# STeaMi-FP6-Microcontroleur.net
KiCad netlist of a schematic drawn in Altium Designer
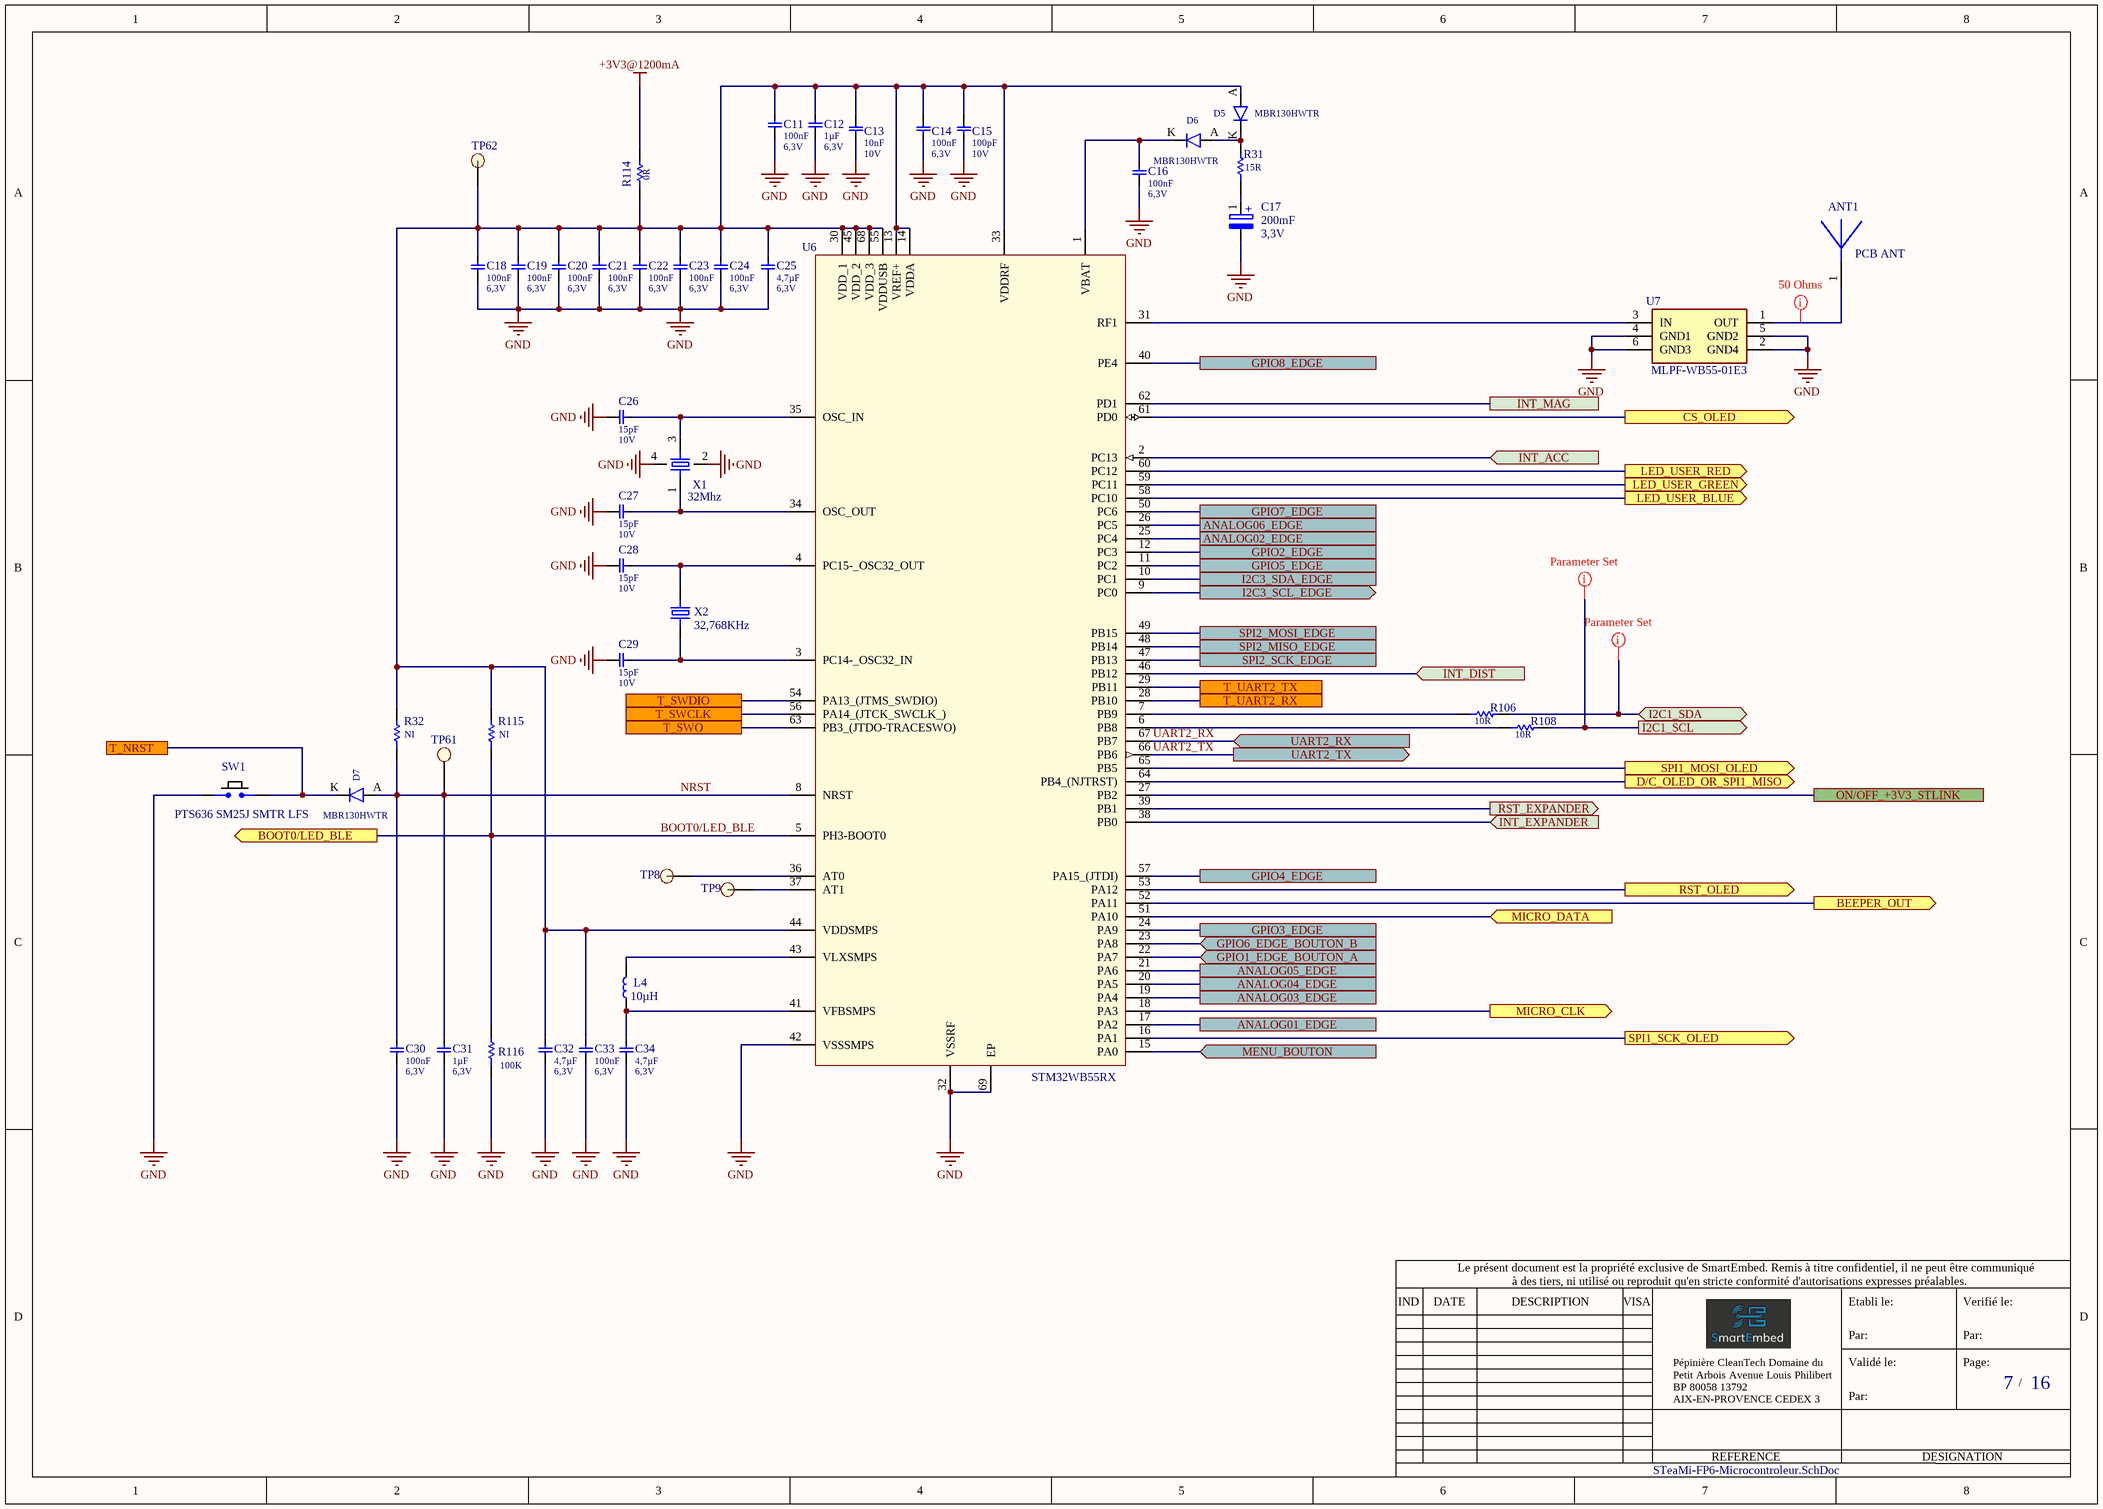
[diagram p0: STeaMi-FP6-Microcontroleur.SchDoc]

(export (version "E")
  (design (tool "Eeschema 10.0.6"))
  (components
    (comp (ref "ANT1")
      (value "PCB ANT")
      (footprint "PCB_ANT")
      (description "PCB ANTENAL")
      (fields (field (name "PART NUMBER") "PCB_ANT") (field (name "CREATED BY") "EAG"))
      (libsource (lib "ComponentDB") (part "NN01-102"))
    )
    (comp (ref "C11")
      (value "~")
      (footprint "0402-CAP")
      (description "CAP CER 100nF 6,3V X5R 0402")
      (fields
        (field (name "MANUFACTURER") "Kyocera AVX")
        (field (name "MANUFACTURER PART NUMBER") "0402YD104KAT2A")
        (field (name "CAPACITANCE") "100nF")
        (field (name "VOLTAGE") "6,3V")
        (field (name "CREATED BY") "EAG")
        (field (name "CHECKED BY") "*")
      )
      (libsource (lib "ComponentDB") (part "CAP_SYMBOL"))
    )
    (comp (ref "C12")
      (value "~")
      (footprint "0402-CAP")
      (description "CAP CER 1µF 6,3V X5R 0402")
      (fields
        (field (name "MANUFACTURER") "Taiyo Yuden")
        (field (name "MANUFACTURER PART NUMBER") "JMK105BJ105KV-F")
        (field (name "CAPACITANCE") "1µF")
        (field (name "VOLTAGE") "6,3V")
        (field (name "CREATED BY") "EAG")
        (field (name "CHECKED BY") "*")
      )
      (libsource (lib "ComponentDB") (part "CAP_SYMBOL"))
    )
    (comp (ref "C13")
      (value "~")
      (footprint "0402-CAP")
      (description "CAP CER 10nF 10V X7R 0402")
      (fields
        (field (name "MANUFACTURER") "AVX")
        (field (name "MANUFACTURER PART NUMBER") "0402ZC103KAT2A")
        (field (name "CAPACITANCE") "10nF")
        (field (name "VOLTAGE") "10V")
        (field (name "CREATED BY") "EAG")
        (field (name "CHECKED BY") "*")
      )
      (libsource (lib "ComponentDB") (part "CAP_SYMBOL"))
    )
    (comp (ref "C14")
      (value "~")
      (footprint "0402-CAP")
      (description "CAP CER 100nF 6,3V X5R 0402")
      (fields
        (field (name "MANUFACTURER") "Kyocera AVX")
        (field (name "MANUFACTURER PART NUMBER") "0402YD104KAT2A")
        (field (name "CAPACITANCE") "100nF")
        (field (name "VOLTAGE") "6,3V")
        (field (name "CREATED BY") "EAG")
        (field (name "CHECKED BY") "*")
      )
      (libsource (lib "ComponentDB") (part "CAP_SYMBOL"))
    )
    (comp (ref "C15")
      (value "~")
      (footprint "0402-CAP")
      (description "CAP CER 100pF 10V X7R 0402")
      (fields
        (field (name "MANUFACTURER") "WURTH Electronics")
        (field (name "MANUFACTURER PART NUMBER") "885012205001")
        (field (name "CAPACITANCE") "100pF")
        (field (name "VOLTAGE") "10V")
        (field (name "CREATED BY") "EAG")
        (field (name "CHECKED BY") "*")
      )
      (libsource (lib "ComponentDB") (part "CAP_SYMBOL"))
    )
    (comp (ref "C16")
      (value "~")
      (footprint "0402-CAP")
      (description "CAP CER 100nF 6,3V X5R 0402")
      (fields
        (field (name "MANUFACTURER") "Kyocera AVX")
        (field (name "MANUFACTURER PART NUMBER") "0402YD104KAT2A")
        (field (name "CAPACITANCE") "100nF")
        (field (name "VOLTAGE") "6,3V")
        (field (name "CREATED BY") "EAG")
        (field (name "CHECKED BY") "*")
      )
      (libsource (lib "ComponentDB") (part "CAP_SYMBOL"))
    )
    (comp (ref "C17")
      (value "~")
      (footprint "DSK3R3H204T614")
      (description "CAP CER 200mF 3,3V Supercap 6,8X11,7x1,8")
      (fields
        (field (name "MANUFACTURER") "Elna America")
        (field (name "MANUFACTURER PART NUMBER") "DSK-3R3H204T614-H2L")
        (field (name "CAPACITANCE") "200mF")
        (field (name "VOLTAGE") "3,3V")
        (field (name "CREATED BY") "EAG")
      )
      (libsource (lib "ComponentDB") (part "CAP_POL_SYMBOL"))
    )
    (comp (ref "C18")
      (value "~")
      (footprint "0402-CAP")
      (description "CAP CER 100nF 6,3V X5R 0402")
      (fields
        (field (name "MANUFACTURER") "Kyocera AVX")
        (field (name "MANUFACTURER PART NUMBER") "0402YD104KAT2A")
        (field (name "CAPACITANCE") "100nF")
        (field (name "VOLTAGE") "6,3V")
        (field (name "CREATED BY") "EAG")
        (field (name "CHECKED BY") "*")
      )
      (libsource (lib "ComponentDB") (part "CAP_SYMBOL"))
    )
    (comp (ref "C19")
      (value "~")
      (footprint "0402-CAP")
      (description "CAP CER 100nF 6,3V X5R 0402")
      (fields
        (field (name "MANUFACTURER") "Kyocera AVX")
        (field (name "MANUFACTURER PART NUMBER") "0402YD104KAT2A")
        (field (name "CAPACITANCE") "100nF")
        (field (name "VOLTAGE") "6,3V")
        (field (name "CREATED BY") "EAG")
        (field (name "CHECKED BY") "*")
      )
      (libsource (lib "ComponentDB") (part "CAP_SYMBOL"))
    )
    (comp (ref "C20")
      (value "~")
      (footprint "0402-CAP")
      (description "CAP CER 100nF 6,3V X5R 0402")
      (fields
        (field (name "MANUFACTURER") "Kyocera AVX")
        (field (name "MANUFACTURER PART NUMBER") "0402YD104KAT2A")
        (field (name "CAPACITANCE") "100nF")
        (field (name "VOLTAGE") "6,3V")
        (field (name "CREATED BY") "EAG")
        (field (name "CHECKED BY") "*")
      )
      (libsource (lib "ComponentDB") (part "CAP_SYMBOL"))
    )
    (comp (ref "C21")
      (value "~")
      (footprint "0402-CAP")
      (description "CAP CER 100nF 6,3V X5R 0402")
      (fields
        (field (name "MANUFACTURER") "Kyocera AVX")
        (field (name "MANUFACTURER PART NUMBER") "0402YD104KAT2A")
        (field (name "CAPACITANCE") "100nF")
        (field (name "VOLTAGE") "6,3V")
        (field (name "CREATED BY") "EAG")
        (field (name "CHECKED BY") "*")
      )
      (libsource (lib "ComponentDB") (part "CAP_SYMBOL"))
    )
    (comp (ref "C22")
      (value "~")
      (footprint "0402-CAP")
      (description "CAP CER 100nF 6,3V X5R 0402")
      (fields
        (field (name "MANUFACTURER") "Kyocera AVX")
        (field (name "MANUFACTURER PART NUMBER") "0402YD104KAT2A")
        (field (name "CAPACITANCE") "100nF")
        (field (name "VOLTAGE") "6,3V")
        (field (name "CREATED BY") "EAG")
        (field (name "CHECKED BY") "*")
      )
      (libsource (lib "ComponentDB") (part "CAP_SYMBOL"))
    )
    (comp (ref "C23")
      (value "~")
      (footprint "0402-CAP")
      (description "CAP CER 100nF 6,3V X5R 0402")
      (fields
        (field (name "MANUFACTURER") "Kyocera AVX")
        (field (name "MANUFACTURER PART NUMBER") "0402YD104KAT2A")
        (field (name "CAPACITANCE") "100nF")
        (field (name "VOLTAGE") "6,3V")
        (field (name "CREATED BY") "EAG")
        (field (name "CHECKED BY") "*")
      )
      (libsource (lib "ComponentDB") (part "CAP_SYMBOL"))
    )
    (comp (ref "C24")
      (value "~")
      (footprint "0402-CAP")
      (description "CAP CER 100nF 6,3V X5R 0402")
      (fields
        (field (name "MANUFACTURER") "Kyocera AVX")
        (field (name "MANUFACTURER PART NUMBER") "0402YD104KAT2A")
        (field (name "CAPACITANCE") "100nF")
        (field (name "VOLTAGE") "6,3V")
        (field (name "CREATED BY") "EAG")
        (field (name "CHECKED BY") "*")
      )
      (libsource (lib "ComponentDB") (part "CAP_SYMBOL"))
    )
    (comp (ref "C25")
      (value "~")
      (footprint "0402-CAP")
      (description "CAP CER 4,7µF 6,3V X5R 0402")
      (fields
        (field (name "MANUFACTURER") "Murata")
        (field (name "MANUFACTURER PART NUMBER") "GRM155R60J475ME8D")
        (field (name "CAPACITANCE") "4,7µF")
        (field (name "VOLTAGE") "6,3V")
        (field (name "CREATED BY") "EAG")
        (field (name "CHECKED BY") "*")
      )
      (libsource (lib "ComponentDB") (part "CAP_SYMBOL"))
    )
    (comp (ref "C26")
      (value "~")
      (footprint "0402-CAP")
      (description "CAP CER 15pF 10V C0G 0402")
      (fields
        (field (name "MANUFACTURER") "KEMET")
        (field (name "MANUFACTURER PART NUMBER") "C0402C150J8HACTU")
        (field (name "CAPACITANCE") "15pF")
        (field (name "VOLTAGE") "10V")
        (field (name "CREATED BY") "EAG")
        (field (name "CHECKED BY") "*")
      )
      (libsource (lib "ComponentDB") (part "CAP_SYMBOL"))
    )
    (comp (ref "C27")
      (value "~")
      (footprint "0402-CAP")
      (description "CAP CER 15pF 10V C0G 0402")
      (fields
        (field (name "MANUFACTURER") "KEMET")
        (field (name "MANUFACTURER PART NUMBER") "C0402C150J8HACTU")
        (field (name "CAPACITANCE") "15pF")
        (field (name "VOLTAGE") "10V")
        (field (name "CREATED BY") "EAG")
        (field (name "CHECKED BY") "*")
      )
      (libsource (lib "ComponentDB") (part "CAP_SYMBOL"))
    )
    (comp (ref "C28")
      (value "~")
      (footprint "0402-CAP")
      (description "CAP CER 15pF 10V C0G 0402")
      (fields
        (field (name "MANUFACTURER") "KEMET")
        (field (name "MANUFACTURER PART NUMBER") "C0402C150J8HACTU")
        (field (name "CAPACITANCE") "15pF")
        (field (name "VOLTAGE") "10V")
        (field (name "CREATED BY") "EAG")
        (field (name "CHECKED BY") "*")
      )
      (libsource (lib "ComponentDB") (part "CAP_SYMBOL"))
    )
    (comp (ref "C29")
      (value "~")
      (footprint "0402-CAP")
      (description "CAP CER 15pF 10V C0G 0402")
      (fields
        (field (name "MANUFACTURER") "KEMET")
        (field (name "MANUFACTURER PART NUMBER") "C0402C150J8HACTU")
        (field (name "CAPACITANCE") "15pF")
        (field (name "VOLTAGE") "10V")
        (field (name "CREATED BY") "EAG")
        (field (name "CHECKED BY") "*")
      )
      (libsource (lib "ComponentDB") (part "CAP_SYMBOL"))
    )
    (comp (ref "C30")
      (value "~")
      (footprint "0402-CAP")
      (description "CAP CER 100nF 6,3V X5R 0402")
      (fields
        (field (name "MANUFACTURER") "Kyocera AVX")
        (field (name "MANUFACTURER PART NUMBER") "0402YD104KAT2A")
        (field (name "CAPACITANCE") "100nF")
        (field (name "VOLTAGE") "6,3V")
        (field (name "CREATED BY") "EAG")
        (field (name "CHECKED BY") "*")
      )
      (libsource (lib "ComponentDB") (part "CAP_SYMBOL"))
    )
    (comp (ref "C31")
      (value "~")
      (footprint "0402-CAP")
      (description "CAP CER 1µF 6,3V X5R 0402")
      (fields
        (field (name "MANUFACTURER") "Taiyo Yuden")
        (field (name "MANUFACTURER PART NUMBER") "JMK105BJ105KV-F")
        (field (name "CAPACITANCE") "1µF")
        (field (name "VOLTAGE") "6,3V")
        (field (name "CREATED BY") "EAG")
        (field (name "CHECKED BY") "*")
      )
      (libsource (lib "ComponentDB") (part "CAP_SYMBOL"))
    )
    (comp (ref "C32")
      (value "~")
      (footprint "0402-CAP")
      (description "CAP CER 4,7µF 6,3V X5R 0402")
      (fields
        (field (name "CAPACITANCE") "4,7µF")
        (field (name "VOLTAGE") "6,3V")
        (field (name "PART NUMBER") "4,7µF-20%-6,3V-X5R-0402")
        (field (name "CREATED BY") "EAG")
        (field (name "CHECKED BY") "*")
      )
      (libsource (lib "ComponentDB") (part "CAP_SYMBOL"))
    )
    (comp (ref "C33")
      (value "~")
      (footprint "0402-CAP")
      (description "CAP CER 100nF 6,3V X5R 0402")
      (fields
        (field (name "MANUFACTURER") "Kyocera AVX")
        (field (name "MANUFACTURER PART NUMBER") "0402YD104KAT2A")
        (field (name "CAPACITANCE") "100nF")
        (field (name "VOLTAGE") "6,3V")
        (field (name "CREATED BY") "EAG")
        (field (name "CHECKED BY") "*")
      )
      (libsource (lib "ComponentDB") (part "CAP_SYMBOL"))
    )
    (comp (ref "C34")
      (value "~")
      (footprint "0402-CAP")
      (description "CAP CER 4,7µF 6,3V X5R 0402")
      (fields
        (field (name "CAPACITANCE") "4,7µF")
        (field (name "VOLTAGE") "6,3V")
        (field (name "PART NUMBER") "4,7µF-20%-6,3V-X5R-0402")
        (field (name "CREATED BY") "EAG")
        (field (name "CHECKED BY") "*")
      )
      (libsource (lib "ComponentDB") (part "CAP_SYMBOL"))
    )
    (comp (ref "D5")
      (value "~")
      (footprint "SOD3615X145N_SOD123")
      (description "Diode Schottky 30 V 1A Montage en surface SOD-123")
      (fields
        (field (name "MANUFACTURER") "SMC diode solutions")
        (field (name "MANUFACTURER PART NUMBER") "MBR130HWTR")
        (field (name "PART NUMBER") "MBR130HWTR")
        (field (name "CREATED BY") "EAG")
      )
      (libsource (lib "ComponentDB") (part "DIODE_SYMBOL"))
    )
    (comp (ref "D6")
      (value "~")
      (footprint "SOD3615X145N_SOD123")
      (description "Diode Schottky 30 V 1A Montage en surface SOD-123")
      (fields
        (field (name "MANUFACTURER") "SMC diode solutions")
        (field (name "MANUFACTURER PART NUMBER") "MBR130HWTR")
        (field (name "PART NUMBER") "MBR130HWTR")
        (field (name "CREATED BY") "EAG")
      )
      (libsource (lib "ComponentDB") (part "DIODE_SYMBOL"))
    )
    (comp (ref "D7")
      (value "~")
      (footprint "SOD3615X145N_SOD123")
      (description "Diode Schottky 30 V 1A Montage en surface SOD-123")
      (fields
        (field (name "MANUFACTURER") "SMC diode solutions")
        (field (name "MANUFACTURER PART NUMBER") "MBR130HWTR")
        (field (name "PART NUMBER") "MBR130HWTR")
        (field (name "CREATED BY") "EAG")
      )
      (libsource (lib "ComponentDB") (part "DIODE_SYMBOL"))
    )
    (comp (ref "L4")
      (value "~")
      (footprint "LQM21 SERIES")
      (description "Fixed Inductor 10µH µH ± 20% 0,1A 0805")
      (fields
        (field (name "MANUFACTURER") "Murata Electronics")
        (field (name "MANUFACTURER PART NUMBER") "LQM21FN100M70L")
        (field (name "INDUCTANCE") "10µH")
        (field (name "CREATED BY") "EAG")
      )
      (libsource (lib "ComponentDB") (part "BOB_SYMBOL"))
    )
    (comp (ref "R31")
      (value "~")
      (footprint "RESC3216X88N_1206")
      (description "RES CMS 15R0,5%-1W-1206 ±0ppm/°C")
      (fields
        (field (name "MANUFACTURER") "Susumu")
        (field (name "MANUFACTURER PART NUMBER") "HRG3216Q-15R0-D-T1")
        (field (name "RESISTANCE") "15R")
        (field (name "CREATED BY") "EAG")
      )
      (libsource (lib "ComponentDB") (part "RES_SYMBOL"))
    )
    (comp (ref "R32")
      (value "~")
      (footprint "RESC1005X40N_0402")
      (description "NI")
      (fields
        (field (name "POWER") "0,1")
        (field (name "RESISTANCE") "NI")
        (field (name "PART NUMBER") "NI-1%-0,1W-0603")
        (field (name "CREATED BY") "MSA")
      )
      (libsource (lib "ComponentDB") (part "RES_SYMBOL"))
    )
    (comp (ref "R106")
      (value "~")
      (footprint "RESC1005X40N_0402")
      (description "RES CMS 10R1%-0,0625W-0402 ±200ppm/°C")
      (fields
        (field (name "MANUFACTURER") "Yageo")
        (field (name "MANUFACTURER PART NUMBER") "RC0402FR-1010RL")
        (field (name "RESISTANCE") "10R")
        (field (name "CREATED BY") "EAG")
      )
      (libsource (lib "ComponentDB") (part "RES_SYMBOL"))
    )
    (comp (ref "R108")
      (value "~")
      (footprint "RESC1005X40N_0402")
      (description "RES CMS 10R1%-0,0625W-0402 ±200ppm/°C")
      (fields
        (field (name "MANUFACTURER") "Yageo")
        (field (name "MANUFACTURER PART NUMBER") "RC0402FR-1010RL")
        (field (name "RESISTANCE") "10R")
        (field (name "CREATED BY") "EAG")
      )
      (libsource (lib "ComponentDB") (part "RES_SYMBOL"))
    )
    (comp (ref "R114")
      (value "~")
      (footprint "RESC1005X40N_0402")
      (description "RES CMS 0R5%-0,0625W-0402")
      (fields
        (field (name "MANUFACTURER") "Yageo")
        (field (name "MANUFACTURER PART NUMBER") "RC0402JR-100RL")
        (field (name "RESISTANCE") "0R")
        (field (name "CREATED BY") "EAG")
      )
      (libsource (lib "ComponentDB") (part "RES_SYMBOL"))
    )
    (comp (ref "R115")
      (value "~")
      (footprint "RESC1005X40N_0402")
      (description "NI")
      (fields
        (field (name "POWER") "0,1")
        (field (name "RESISTANCE") "NI")
        (field (name "PART NUMBER") "NI-1%-0,1W-0603")
        (field (name "CREATED BY") "MSA")
      )
      (libsource (lib "ComponentDB") (part "RES_SYMBOL"))
    )
    (comp (ref "R116")
      (value "~")
      (footprint "RESC1005X40N_0402")
      (description "RES CMS 100K1%-0,063W-0402 ±100ppm/°C")
      (fields
        (field (name "MANUFACTURER") "TE Connectivity")
        (field (name "MANUFACTURER PART NUMBER") "CRG0402F100K")
        (field (name "RESISTANCE") "100K")
        (field (name "CREATED BY") "EAG")
      )
      (libsource (lib "ComponentDB") (part "RES_SYMBOL"))
    )
    (comp (ref "SW1")
      (value "~")
      (footprint "PTS636SM25FSMTRLFS")
      (description "Surface Mounting Switch")
      (fields
        (field (name "MANUFACTURER") "C&K")
        (field (name "MANUFACTURER PART NUMBER") "PTS636 SM25J SMTR LFS")
        (field (name "PART NUMBER") "PTS636 SM25J SMTR LFS")
        (field (name "CREATED BY") "EAG")
        (field (name "CHECKED BY") "*")
      )
      (libsource (lib "ComponentDB") (part "B3U1000P"))
    )
    (comp (ref "TP8")
      (value "PAD")
      (footprint "Testpoint 1mm")
      (description "TESTPOINTPAD")
      (fields
        (field (name "MANUFACTURER") "Smartembed")
        (field (name "MANUFACTURER PART NUMBER") "TESTPOINT")
        (field (name "CREATED BY") "EAG")
      )
      (libsource (lib "ComponentDB") (part "TESTPOINT"))
    )
    (comp (ref "TP9")
      (value "PAD")
      (footprint "Testpoint 1mm")
      (description "TESTPOINTPAD")
      (fields
        (field (name "MANUFACTURER") "Smartembed")
        (field (name "MANUFACTURER PART NUMBER") "TESTPOINT")
        (field (name "CREATED BY") "EAG")
      )
      (libsource (lib "ComponentDB") (part "TESTPOINT"))
    )
    (comp (ref "TP61")
      (value "PAD")
      (footprint "Testpoint 1mm")
      (description "TESTPOINTPAD")
      (fields
        (field (name "MANUFACTURER") "Smartembed")
        (field (name "MANUFACTURER PART NUMBER") "TESTPOINT")
        (field (name "CREATED BY") "EAG")
      )
      (libsource (lib "") (part "TESTPOINT_1"))
    )
    (comp (ref "TP62")
      (value "PAD")
      (footprint "Testpoint 1mm")
      (description "TESTPOINTPAD")
      (fields
        (field (name "MANUFACTURER") "Smartembed")
        (field (name "MANUFACTURER PART NUMBER") "TESTPOINT")
        (field (name "CREATED BY") "EAG")
      )
      (libsource (lib "ComponentDB") (part "TESTPOINT"))
    )
    (comp (ref "U6")
      (value "~")
      (footprint "QFN40P800X800X100-69N-D")
      (description "MCU 32bit, STM32WB55RX-M4, 256 Kb to 1Mb Flash 128 to 256kB SRAM 64MHz Bluetooth 5.2, VFQFPN68")
      (fields
        (field (name "MANUFACTURER") "STMicroelectronics")
        (field (name "MANUFACTURER PART NUMBER") "STM32WB55RX")
        (field (name "PART NUMBER") "STM32WB55RX")
        (field (name "CREATED BY") "EAG")
        (field (name "CHECKED BY") "*")
      )
      (libsource (lib "ComponentDB") (part "STM32WB55RX"))
    )
    (comp (ref "U7")
      (value "~")
      (footprint "MLPFWB5501E3")
      (fields
        (field (name "MANUFACTURER") "STMicroelectronics")
        (field (name "MANUFACTURER PART NUMBER") "MLPF-WB55-01E3")
        (field (name "PART NUMBER") "MLPF-WB55-01E3")
        (field (name "CREATED BY") "EAG")
        (field (name "CHECKED BY") "*")
      )
      (libsource (lib "ComponentDB") (part "MLPF-WB55-01E3"))
    )
    (comp (ref "X1")
      (value "~")
      (footprint "WE_XTAL_CFPX_180")
      (description "QUARTZ 32MHz 9pF 10 ppm")
      (fields
        (field (name "MANUFACTURER PART NUMBER") "830103552209")
        (field (name "MANUFACTURER") "Wurth")
        (field (name "FREQUENCY") "32Mhz")
        (field (name "CREATED BY") "EAG")
      )
      (libsource (lib "ComponentDB") (part "4PIN"))
    )
    (comp (ref "X2")
      (value "~")
      (footprint "WE_XTAL_IQXC-25")
      (description "QUARTZ 32Khz 12pF 30 ppm")
      (fields
        (field (name "MANUFACTURER PART NUMBER") "830062558")
        (field (name "MANUFACTURER") "Wurth")
        (field (name "FREQUENCY") "32,768KHz")
        (field (name "CREATED BY") "EAG")
      )
      (libsource (lib "ComponentDB") (part "2PIN"))
    )
  )
  (nets
    (net (code "1") (name "+3V3@1200mA") (class "Default")
      (node (ref "R114") (pin "2") (pinfunction "2_2") (pintype "passive"))
    )
    (net (code "2") (name "/ANALOG01_EDGE") (class "Default")
      (node (ref "U6") (pin "17") (pinfunction "PA2_17") (pintype "passive"))
    )
    (net (code "3") (name "/ANALOG02_EDGE") (class "Default")
      (node (ref "U6") (pin "25") (pinfunction "PC4_25") (pintype "passive"))
    )
    (net (code "4") (name "/ANALOG03_EDGE") (class "Default")
      (node (ref "U6") (pin "19") (pinfunction "PA4_19") (pintype "passive"))
    )
    (net (code "5") (name "/ANALOG04_EDGE") (class "Default")
      (node (ref "U6") (pin "20") (pinfunction "PA5_20") (pintype "passive"))
    )
    (net (code "6") (name "/ANALOG05_EDGE") (class "Default")
      (node (ref "U6") (pin "21") (pinfunction "PA6_21") (pintype "passive"))
    )
    (net (code "7") (name "/ANALOG06_EDGE") (class "Default")
      (node (ref "U6") (pin "26") (pinfunction "PC5_26") (pintype "passive"))
    )
    (net (code "8") (name "/BEEPER_OUT") (class "Default")
      (node (ref "U6") (pin "52") (pinfunction "PA11_52") (pintype "passive"))
    )
    (net (code "9") (name "/BOOT0{slash}LED_BLE") (class "Default")
      (node (ref "R115") (pin "1") (pinfunction "1_1") (pintype "passive"))
      (node (ref "R116") (pin "2") (pinfunction "2_2") (pintype "passive"))
      (node (ref "U6") (pin "5") (pinfunction "PH3-BOOT0_5") (pintype "passive"))
    )
    (net (code "10") (name "/CS_OLED") (class "Default")
      (node (ref "U6") (pin "61") (pinfunction "PD0_61") (pintype "bidirectional"))
    )
    (net (code "11") (name "/D{slash}C_OLED_OR_SPI1_MISO") (class "Default")
      (node (ref "U6") (pin "64") (pinfunction "PB4_(NJTRST)_64") (pintype "passive"))
    )
    (net (code "12") (name "/GPIO1_EDGE_BOUTON_A") (class "Default")
      (node (ref "U6") (pin "22") (pinfunction "PA7_22") (pintype "passive"))
    )
    (net (code "13") (name "/GPIO2_EDGE") (class "Default")
      (node (ref "U6") (pin "12") (pinfunction "PC3_12") (pintype "passive"))
    )
    (net (code "14") (name "/GPIO3_EDGE") (class "Default")
      (node (ref "U6") (pin "24") (pinfunction "PA9_24") (pintype "passive"))
    )
    (net (code "15") (name "/GPIO4_EDGE") (class "Default")
      (node (ref "U6") (pin "57") (pinfunction "PA15_(JTDI)_57") (pintype "passive"))
    )
    (net (code "16") (name "/GPIO5_EDGE") (class "Default")
      (node (ref "U6") (pin "11") (pinfunction "PC2_11") (pintype "passive"))
    )
    (net (code "17") (name "/GPIO6_EDGE_BOUTON_B") (class "Default")
      (node (ref "U6") (pin "23") (pinfunction "PA8_23") (pintype "passive"))
    )
    (net (code "18") (name "/GPIO7_EDGE") (class "Default")
      (node (ref "U6") (pin "50") (pinfunction "PC6_50") (pintype "passive"))
    )
    (net (code "19") (name "/GPIO8_EDGE") (class "Default")
      (node (ref "U6") (pin "40") (pinfunction "PE4_40") (pintype "passive"))
    )
    (net (code "20") (name "/I2C1_SCL") (class "Default")
      (node (ref "R108") (pin "2") (pinfunction "2_2") (pintype "passive"))
    )
    (net (code "21") (name "/I2C1_SDA") (class "Default")
      (node (ref "R106") (pin "2") (pinfunction "2_2") (pintype "passive"))
    )
    (net (code "22") (name "/I2C3_SCL_EDGE") (class "Default")
      (node (ref "U6") (pin "9") (pinfunction "PC0_9") (pintype "passive"))
    )
    (net (code "23") (name "/I2C3_SDA_EDGE") (class "Default")
      (node (ref "U6") (pin "10") (pinfunction "PC1_10") (pintype "passive"))
    )
    (net (code "24") (name "/INT_ACC") (class "Default")
      (node (ref "U6") (pin "2") (pinfunction "PC13_2") (pintype "input"))
    )
    (net (code "25") (name "/INT_DIST") (class "Default")
      (node (ref "U6") (pin "46") (pinfunction "PB12_46") (pintype "passive"))
    )
    (net (code "26") (name "/INT_EXPANDER") (class "Default")
      (node (ref "U6") (pin "38") (pinfunction "PB0_38") (pintype "passive"))
    )
    (net (code "27") (name "/INT_MAG") (class "Default")
      (node (ref "U6") (pin "62") (pinfunction "PD1_62") (pintype "passive"))
    )
    (net (code "28") (name "/LED_USER_BLUE") (class "Default")
      (node (ref "U6") (pin "58") (pinfunction "PC10_58") (pintype "passive"))
    )
    (net (code "29") (name "/LED_USER_GREEN") (class "Default")
      (node (ref "U6") (pin "59") (pinfunction "PC11_59") (pintype "passive"))
    )
    (net (code "30") (name "/LED_USER_RED") (class "Default")
      (node (ref "U6") (pin "60") (pinfunction "PC12_60") (pintype "passive"))
    )
    (net (code "31") (name "/MENU_BOUTON") (class "Default")
      (node (ref "U6") (pin "15") (pinfunction "PA0_15") (pintype "passive"))
    )
    (net (code "32") (name "/MICRO_CLK") (class "Default")
      (node (ref "U6") (pin "18") (pinfunction "PA3_18") (pintype "passive"))
    )
    (net (code "33") (name "/MICRO_DATA") (class "Default")
      (node (ref "U6") (pin "51") (pinfunction "PA10_51") (pintype "passive"))
    )
    (net (code "34") (name "/NRST") (class "Default")
      (node (ref "C30") (pin "2") (pinfunction "2_2") (pintype "passive"))
      (node (ref "C31") (pin "2") (pinfunction "2_2") (pintype "passive"))
      (node (ref "D7") (pin "A") (pinfunction "A_A") (pintype "passive"))
      (node (ref "R32") (pin "1") (pinfunction "1_1") (pintype "passive"))
      (node (ref "TP61") (pin "1") (pinfunction "1_1") (pintype "passive"))
      (node (ref "U6") (pin "8") (pinfunction "NRST_8") (pintype "passive"))
    )
    (net (code "35") (name "/ON{slash}OFF_+3V3_STLINK") (class "Default")
      (node (ref "U6") (pin "27") (pinfunction "PB2_27") (pintype "passive"))
    )
    (net (code "36") (name "/RST_EXPANDER") (class "Default")
      (node (ref "U6") (pin "39") (pinfunction "PB1_39") (pintype "passive"))
    )
    (net (code "37") (name "/RST_OLED") (class "Default")
      (node (ref "U6") (pin "53") (pinfunction "PA12_53") (pintype "passive"))
    )
    (net (code "38") (name "/SPI1_MOSI_OLED") (class "Default")
      (node (ref "U6") (pin "65") (pinfunction "PB5_65") (pintype "passive"))
    )
    (net (code "39") (name "/SPI1_SCK_OLED") (class "Default")
      (node (ref "U6") (pin "16") (pinfunction "PA1_16") (pintype "passive"))
    )
    (net (code "40") (name "/SPI2_MISO_EDGE") (class "Default")
      (node (ref "U6") (pin "48") (pinfunction "PB14_48") (pintype "passive"))
    )
    (net (code "41") (name "/SPI2_MOSI_EDGE") (class "Default")
      (node (ref "U6") (pin "49") (pinfunction "PB15_49") (pintype "passive"))
    )
    (net (code "42") (name "/SPI2_SCK_EDGE") (class "Default")
      (node (ref "U6") (pin "47") (pinfunction "PB13_47") (pintype "passive"))
    )
    (net (code "43") (name "/T_NRST") (class "Default")
      (node (ref "D7") (pin "K") (pinfunction "K_K") (pintype "passive"))
      (node (ref "SW1") (pin "1") (pinfunction "1_1") (pintype "passive"))
    )
    (net (code "44") (name "/T_SWCLK") (class "Default")
      (node (ref "U6") (pin "56") (pinfunction "PA14_(JTCK_SWCLK_)_56") (pintype "passive"))
    )
    (net (code "45") (name "/T_SWDIO") (class "Default")
      (node (ref "U6") (pin "54") (pinfunction "PA13_(JTMS_SWDIO)_54") (pintype "passive"))
    )
    (net (code "46") (name "/T_SWO") (class "Default")
      (node (ref "U6") (pin "63") (pinfunction "PB3_(JTDO-TRACESWO)_63") (pintype "passive"))
    )
    (net (code "47") (name "/T_UART2_RX") (class "Default")
      (node (ref "U6") (pin "28") (pinfunction "PB10_28") (pintype "passive"))
    )
    (net (code "48") (name "/T_UART2_TX") (class "Default")
      (node (ref "U6") (pin "29") (pinfunction "PB11_29") (pintype "passive"))
    )
    (net (code "49") (name "/UART2_RX") (class "Default")
      (node (ref "U6") (pin "67") (pinfunction "PB7_67") (pintype "passive"))
    )
    (net (code "50") (name "/UART2_TX") (class "Default")
      (node (ref "U6") (pin "66") (pinfunction "PB6_66") (pintype "output"))
    )
    (net (code "51") (name "GND") (class "Default")
      (node (ref "C11") (pin "1") (pinfunction "1_1") (pintype "passive"))
      (node (ref "C12") (pin "1") (pinfunction "1_1") (pintype "passive"))
      (node (ref "C13") (pin "2") (pinfunction "2_2") (pintype "passive"))
      (node (ref "C14") (pin "2") (pinfunction "2_2") (pintype "passive"))
      (node (ref "C15") (pin "2") (pinfunction "2_2") (pintype "passive"))
      (node (ref "C16") (pin "1") (pinfunction "1_1") (pintype "passive"))
      (node (ref "C17") (pin "2") (pinfunction "2_2") (pintype "passive"))
      (node (ref "C18") (pin "1") (pinfunction "1_1") (pintype "passive"))
      (node (ref "C19") (pin "1") (pinfunction "1_1") (pintype "passive"))
      (node (ref "C20") (pin "1") (pinfunction "1_1") (pintype "passive"))
      (node (ref "C21") (pin "1") (pinfunction "1_1") (pintype "passive"))
      (node (ref "C22") (pin "1") (pinfunction "1_1") (pintype "passive"))
      (node (ref "C23") (pin "1") (pinfunction "1_1") (pintype "passive"))
      (node (ref "C24") (pin "1") (pinfunction "1_1") (pintype "passive"))
      (node (ref "C25") (pin "1") (pinfunction "1_1") (pintype "passive"))
      (node (ref "C26") (pin "1") (pinfunction "1_1") (pintype "passive"))
      (node (ref "C27") (pin "1") (pinfunction "1_1") (pintype "passive"))
      (node (ref "C28") (pin "1") (pinfunction "1_1") (pintype "passive"))
      (node (ref "C29") (pin "1") (pinfunction "1_1") (pintype "passive"))
      (node (ref "C30") (pin "1") (pinfunction "1_1") (pintype "passive"))
      (node (ref "C31") (pin "1") (pinfunction "1_1") (pintype "passive"))
      (node (ref "C32") (pin "1") (pinfunction "1_1") (pintype "passive"))
      (node (ref "C33") (pin "1") (pinfunction "1_1") (pintype "passive"))
      (node (ref "C34") (pin "1") (pinfunction "1_1") (pintype "passive"))
      (node (ref "R116") (pin "1") (pinfunction "1_1") (pintype "passive"))
      (node (ref "SW1") (pin "2") (pinfunction "2_2") (pintype "passive"))
      (node (ref "U6") (pin "32") (pinfunction "VSSRF_32") (pintype "passive"))
      (node (ref "U6") (pin "42") (pinfunction "VSSSMPS_42") (pintype "passive"))
      (node (ref "U6") (pin "69") (pinfunction "EP_69") (pintype "passive"))
      (node (ref "U7") (pin "2") (pinfunction "GND4_2") (pintype "passive"))
      (node (ref "U7") (pin "4") (pinfunction "GND1_4") (pintype "passive"))
      (node (ref "U7") (pin "5") (pinfunction "GND2_5") (pintype "passive"))
      (node (ref "U7") (pin "6") (pinfunction "GND3_6") (pintype "passive"))
      (node (ref "X1") (pin "2") (pinfunction "GND_2") (pintype "passive"))
      (node (ref "X1") (pin "4") (pinfunction "GND_4") (pintype "passive"))
    )
    (net (code "52") (name "Net-(ANT1-FEED)") (class "Default")
      (node (ref "ANT1") (pin "1") (pinfunction "FEED_1") (pintype "passive"))
      (node (ref "U7") (pin "1") (pinfunction "OUT_1") (pintype "passive"))
    )
    (net (code "53") (name "Net-(C17-Pad1)") (class "Default")
      (node (ref "C17") (pin "1") (pinfunction "1_1") (pintype "passive"))
      (node (ref "R31") (pin "1") (pinfunction "1_1") (pintype "passive"))
    )
    (net (code "54") (name "Net-(D5-PadK)") (class "Default")
      (node (ref "D5") (pin "K") (pinfunction "K_K") (pintype "passive"))
      (node (ref "D6") (pin "A") (pinfunction "A_A") (pintype "passive"))
      (node (ref "R31") (pin "2") (pinfunction "2_2") (pintype "passive"))
    )
    (net (code "55") (name "Net-(U6-AT0)") (class "Default")
      (node (ref "TP8") (pin "1") (pinfunction "1_1") (pintype "passive"))
      (node (ref "U6") (pin "36") (pinfunction "AT0_36") (pintype "passive"))
    )
    (net (code "56") (name "Net-(U6-AT1)") (class "Default")
      (node (ref "TP9") (pin "1") (pinfunction "1_1") (pintype "passive"))
      (node (ref "U6") (pin "37") (pinfunction "AT1_37") (pintype "passive"))
    )
    (net (code "57") (name "Net-(U6-OSC_IN)") (class "Default")
      (node (ref "C26") (pin "2") (pinfunction "2_2") (pintype "passive"))
      (node (ref "U6") (pin "35") (pinfunction "OSC_IN_35") (pintype "passive"))
      (node (ref "X1") (pin "3") (pinfunction "IN/OUT_3") (pintype "passive"))
    )
    (net (code "58") (name "Net-(U6-OSC_OUT)") (class "Default")
      (node (ref "C27") (pin "2") (pinfunction "2_2") (pintype "passive"))
      (node (ref "U6") (pin "34") (pinfunction "OSC_OUT_34") (pintype "passive"))
      (node (ref "X1") (pin "1") (pinfunction "IN/OUT_1") (pintype "passive"))
    )
    (net (code "59") (name "Net-(U6-PB8)") (class "Default")
      (node (ref "R108") (pin "1") (pinfunction "1_1") (pintype "passive"))
      (node (ref "U6") (pin "6") (pinfunction "PB8_6") (pintype "passive"))
    )
    (net (code "60") (name "Net-(U6-PB9)") (class "Default")
      (node (ref "R106") (pin "1") (pinfunction "1_1") (pintype "passive"))
      (node (ref "U6") (pin "7") (pinfunction "PB9_7") (pintype "passive"))
    )
    (net (code "61") (name "Net-(U6-PC14-_OSC32_IN)") (class "Default")
      (node (ref "C29") (pin "2") (pinfunction "2_2") (pintype "passive"))
      (node (ref "U6") (pin "3") (pinfunction "PC14-_OSC32_IN_3") (pintype "passive"))
      (node (ref "X2") (pin "1") (pinfunction "1_1") (pintype "passive"))
    )
    (net (code "62") (name "Net-(U6-PC15-_OSC32_OUT)") (class "Default")
      (node (ref "C28") (pin "2") (pinfunction "2_2") (pintype "passive"))
      (node (ref "U6") (pin "4") (pinfunction "PC15-_OSC32_OUT_4") (pintype "passive"))
      (node (ref "X2") (pin "2") (pinfunction "2_2") (pintype "passive"))
    )
    (net (code "63") (name "Net-(U6-RF1)") (class "Default")
      (node (ref "U6") (pin "31") (pinfunction "RF1_31") (pintype "passive"))
      (node (ref "U7") (pin "3") (pinfunction "IN_3") (pintype "passive"))
    )
    (net (code "64") (name "Net-(U6-VBAT)") (class "Default")
      (node (ref "C16") (pin "2") (pinfunction "2_2") (pintype "passive"))
      (node (ref "D6") (pin "K") (pinfunction "K_K") (pintype "passive"))
      (node (ref "U6") (pin "1") (pinfunction "VBAT_1") (pintype "passive"))
    )
    (net (code "65") (name "Net-(U6-VDDA)") (class "Default")
      (node (ref "C11") (pin "2") (pinfunction "2_2") (pintype "passive"))
      (node (ref "C12") (pin "2") (pinfunction "2_2") (pintype "passive"))
      (node (ref "C13") (pin "1") (pinfunction "1_1") (pintype "passive"))
      (node (ref "C14") (pin "1") (pinfunction "1_1") (pintype "passive"))
      (node (ref "C15") (pin "1") (pinfunction "1_1") (pintype "passive"))
      (node (ref "C18") (pin "2") (pinfunction "2_2") (pintype "passive"))
      (node (ref "C19") (pin "2") (pinfunction "2_2") (pintype "passive"))
      (node (ref "C20") (pin "2") (pinfunction "2_2") (pintype "passive"))
      (node (ref "C21") (pin "2") (pinfunction "2_2") (pintype "passive"))
      (node (ref "C22") (pin "2") (pinfunction "2_2") (pintype "passive"))
      (node (ref "C23") (pin "2") (pinfunction "2_2") (pintype "passive"))
      (node (ref "C24") (pin "2") (pinfunction "2_2") (pintype "passive"))
      (node (ref "C25") (pin "2") (pinfunction "2_2") (pintype "passive"))
      (node (ref "C32") (pin "2") (pinfunction "2_2") (pintype "passive"))
      (node (ref "C33") (pin "2") (pinfunction "2_2") (pintype "passive"))
      (node (ref "D5") (pin "A") (pinfunction "A_A") (pintype "passive"))
      (node (ref "R114") (pin "1") (pinfunction "1_1") (pintype "passive"))
      (node (ref "R115") (pin "2") (pinfunction "2_2") (pintype "passive"))
      (node (ref "R32") (pin "2") (pinfunction "2_2") (pintype "passive"))
      (node (ref "TP62") (pin "1") (pinfunction "1_1") (pintype "passive"))
      (node (ref "U6") (pin "13") (pinfunction "VREF+_13") (pintype "passive"))
      (node (ref "U6") (pin "14") (pinfunction "VDDA_14") (pintype "passive"))
      (node (ref "U6") (pin "30") (pinfunction "VDD_1_30") (pintype "passive"))
      (node (ref "U6") (pin "33") (pinfunction "VDDRF_33") (pintype "passive"))
      (node (ref "U6") (pin "44") (pinfunction "VDDSMPS_44") (pintype "passive"))
      (node (ref "U6") (pin "45") (pinfunction "VDD_2_45") (pintype "passive"))
      (node (ref "U6") (pin "55") (pinfunction "VDDUSB_55") (pintype "passive"))
      (node (ref "U6") (pin "68") (pinfunction "VDD_3_68") (pintype "passive"))
    )
    (net (code "66") (name "Net-(U6-VFBSMPS)") (class "Default")
      (node (ref "C34") (pin "2") (pinfunction "2_2") (pintype "passive"))
      (node (ref "L4") (pin "1") (pinfunction "1_1") (pintype "passive"))
      (node (ref "U6") (pin "41") (pinfunction "VFBSMPS_41") (pintype "passive"))
    )
    (net (code "67") (name "Net-(U6-VLXSMPS)") (class "Default")
      (node (ref "L4") (pin "2") (pinfunction "2_2") (pintype "passive"))
      (node (ref "U6") (pin "43") (pinfunction "VLXSMPS_43") (pintype "passive"))
    )
  )
)
